# LDO_Regulators.net
KiCad netlist of a schematic drawn in Altium Designer
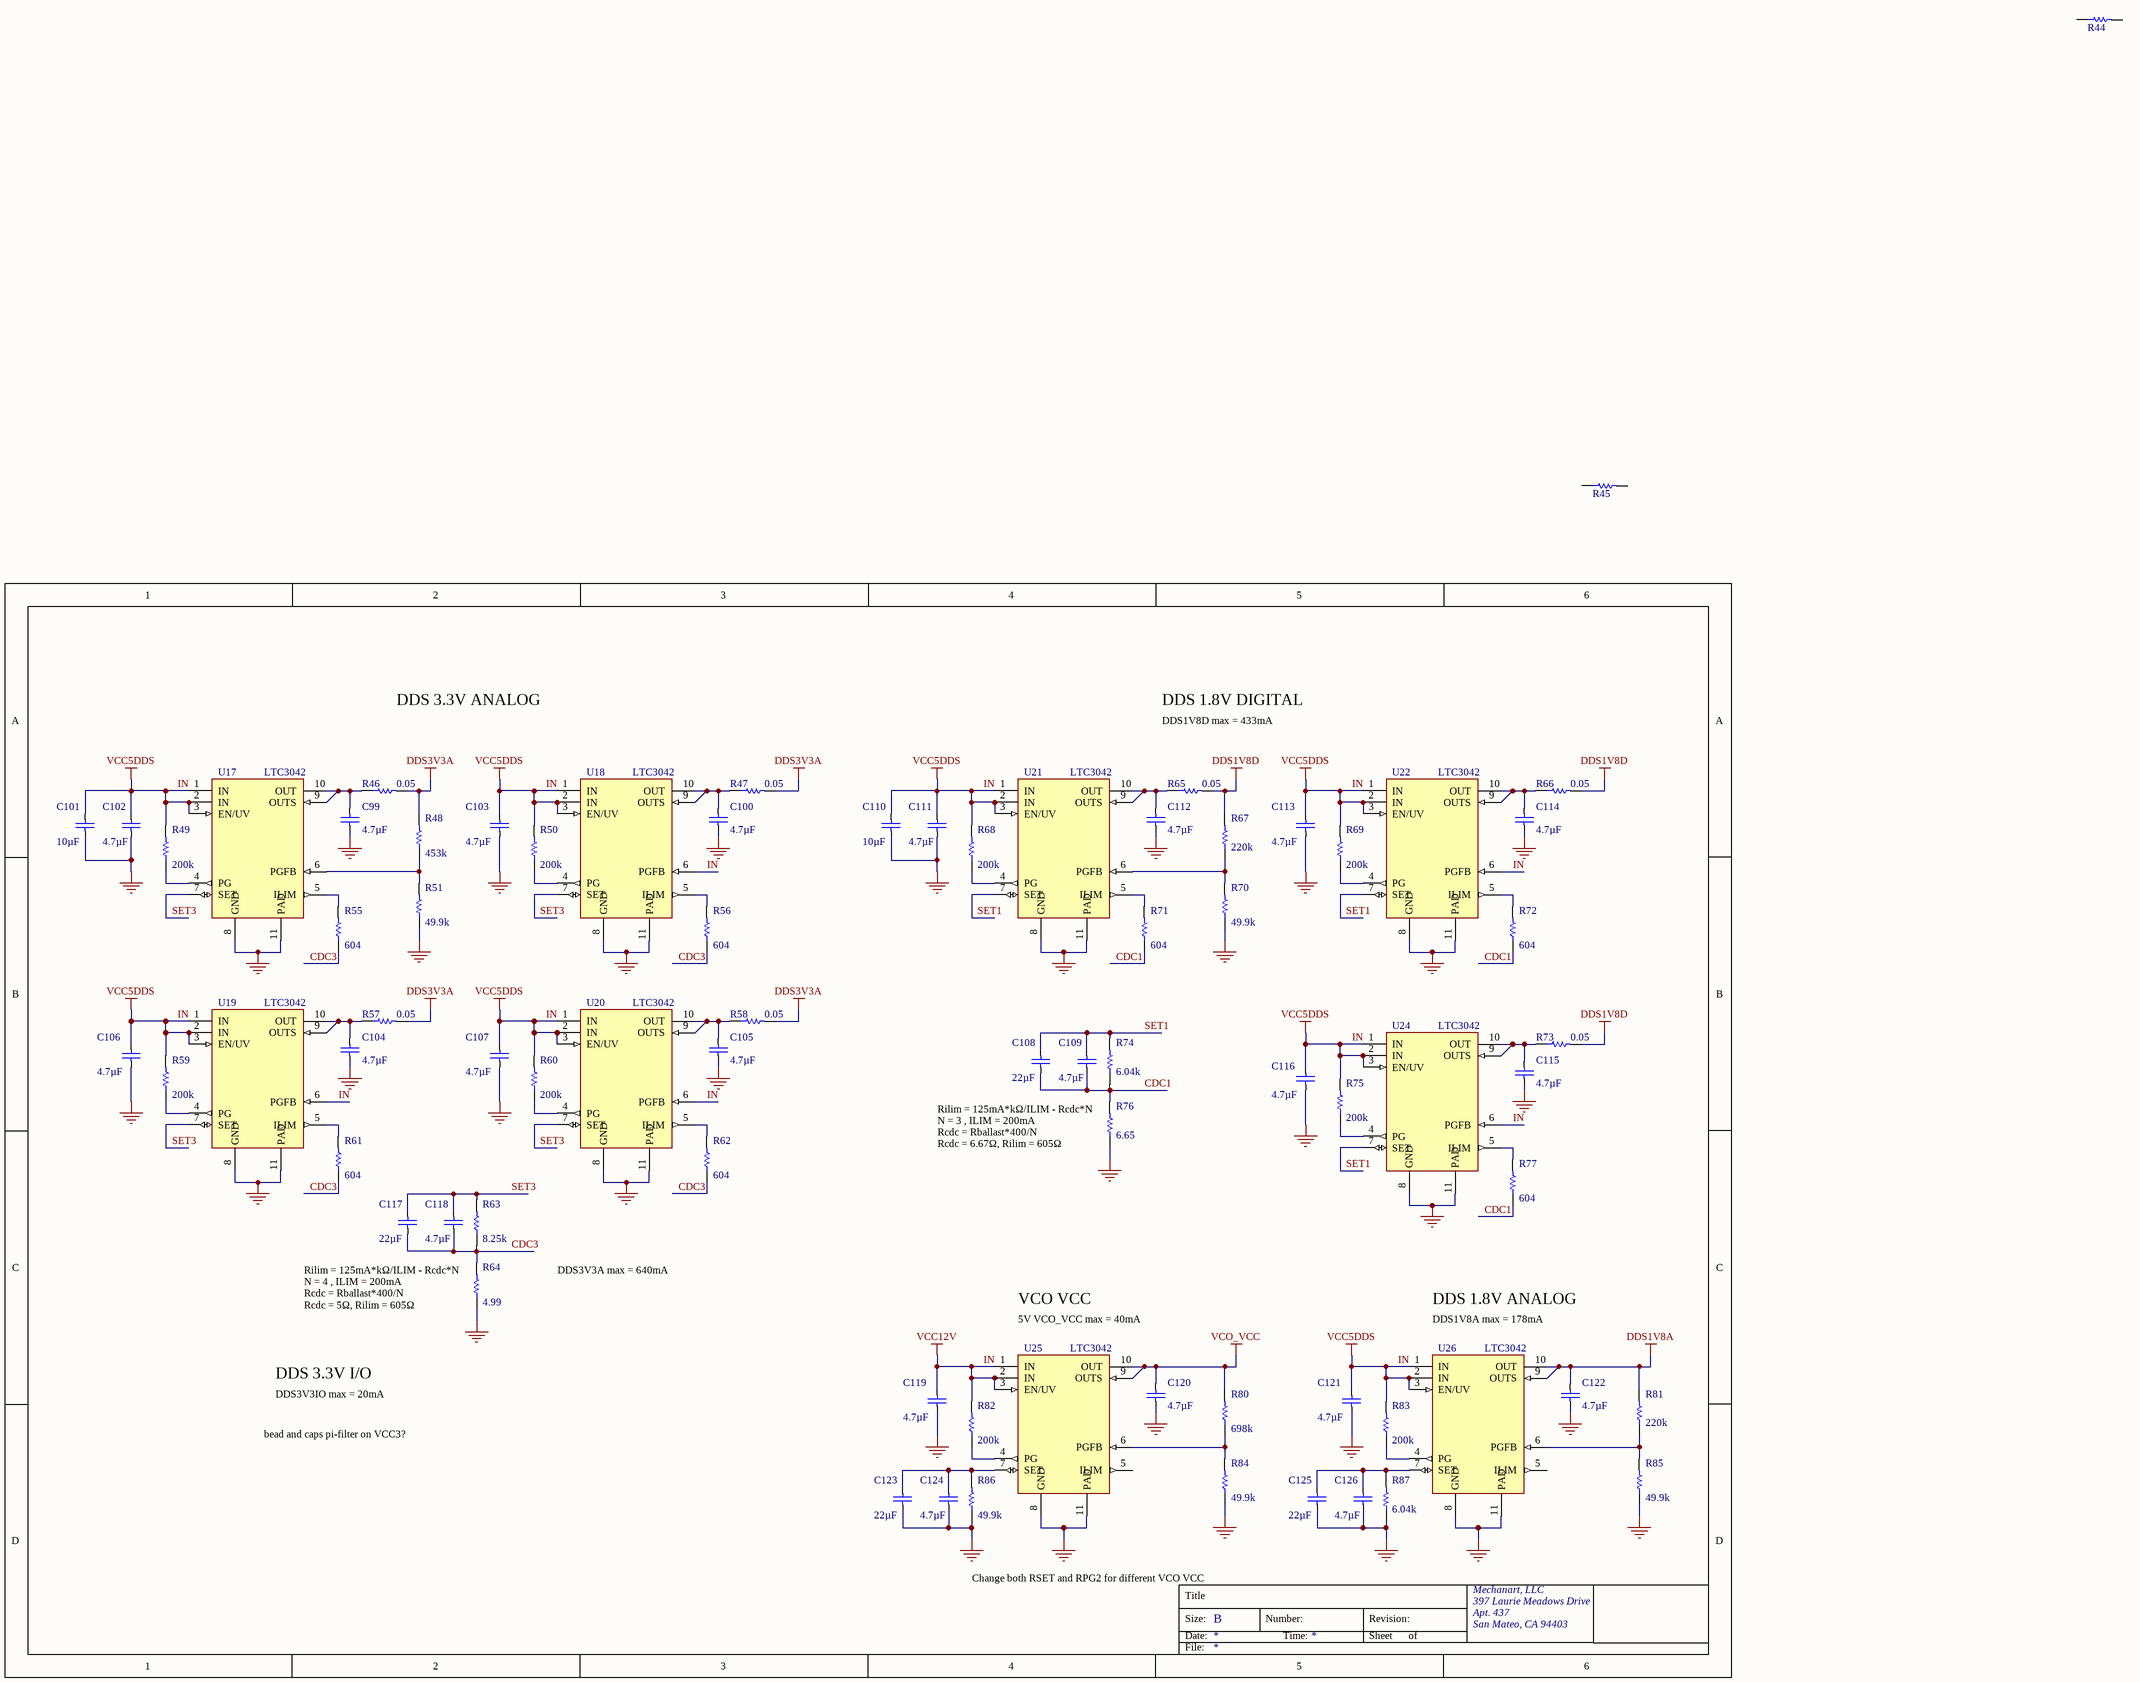
[diagram p0: LDO_Regulators.SchDoc]

(export (version "E")
  (design (tool "Eeschema 10.0.6"))
  (components
    (comp (ref "C99")
      (value "4.7µF")
      (footprint "CAPC3216X160L55N")
      (description "CAP CER 4.7UF 25V X7R 1206")
      (fields
        (field (name "MANUFACTURER") "Murata Electronics North America")
        (field (name "MANUFACTURER PART NUMBER") "GCM31CR71E475KA55L")
      )
      (libsource (lib "mechanart_oshw") (part "CapSMT"))
    )
    (comp (ref "C100")
      (value "4.7µF")
      (footprint "CAPC3216X160L55N")
      (description "CAP CER 4.7UF 25V X7R 1206")
      (fields
        (field (name "MANUFACTURER") "Murata Electronics North America")
        (field (name "MANUFACTURER PART NUMBER") "GCM31CR71E475KA55L")
      )
      (libsource (lib "mechanart_oshw") (part "CapSMT"))
    )
    (comp (ref "C101")
      (value "10µF")
      (footprint "CAPC3216X160L55N")
      (description "CAP CER 10UF 25V X7R 1206")
      (fields
        (field (name "MANUFACTURER") "Murata Electronics North America")
        (field (name "MANUFACTURER PART NUMBER") "GRM31CR71E106KA12L")
      )
      (libsource (lib "mechanart_oshw") (part "CapSMT"))
    )
    (comp (ref "C102")
      (value "4.7µF")
      (footprint "CAPC3216X160L55N")
      (description "CAP CER 4.7UF 25V X7R 1206")
      (fields
        (field (name "MANUFACTURER") "Murata Electronics North America")
        (field (name "MANUFACTURER PART NUMBER") "GCM31CR71E475KA55L")
      )
      (libsource (lib "mechanart_oshw") (part "CapSMT"))
    )
    (comp (ref "C103")
      (value "4.7µF")
      (footprint "CAPC3216X160L55N")
      (description "CAP CER 4.7UF 25V X7R 1206")
      (fields
        (field (name "MANUFACTURER") "Murata Electronics North America")
        (field (name "MANUFACTURER PART NUMBER") "GCM31CR71E475KA55L")
      )
      (libsource (lib "mechanart_oshw") (part "CapSMT"))
    )
    (comp (ref "C104")
      (value "4.7µF")
      (footprint "CAPC3216X160L55N")
      (description "CAP CER 4.7UF 25V X7R 1206")
      (fields
        (field (name "MANUFACTURER") "Murata Electronics North America")
        (field (name "MANUFACTURER PART NUMBER") "GCM31CR71E475KA55L")
      )
      (libsource (lib "mechanart_oshw") (part "CapSMT"))
    )
    (comp (ref "C105")
      (value "4.7µF")
      (footprint "CAPC3216X160L55N")
      (description "CAP CER 4.7UF 25V X7R 1206")
      (fields
        (field (name "MANUFACTURER") "Murata Electronics North America")
        (field (name "MANUFACTURER PART NUMBER") "GCM31CR71E475KA55L")
      )
      (libsource (lib "mechanart_oshw") (part "CapSMT"))
    )
    (comp (ref "C106")
      (value "4.7µF")
      (footprint "CAPC3216X160L55N")
      (description "CAP CER 4.7UF 25V X7R 1206")
      (fields
        (field (name "MANUFACTURER") "Murata Electronics North America")
        (field (name "MANUFACTURER PART NUMBER") "GCM31CR71E475KA55L")
      )
      (libsource (lib "mechanart_oshw") (part "CapSMT"))
    )
    (comp (ref "C107")
      (value "4.7µF")
      (footprint "CAPC3216X160L55N")
      (description "CAP CER 4.7UF 25V X7R 1206")
      (fields
        (field (name "MANUFACTURER") "Murata Electronics North America")
        (field (name "MANUFACTURER PART NUMBER") "GCM31CR71E475KA55L")
      )
      (libsource (lib "mechanart_oshw") (part "CapSMT"))
    )
    (comp (ref "C108")
      (value "22µF")
      (footprint "CAPC2012X145L30N")
      (description "CAP CER 22UF 16V X5R 0805")
      (fields
        (field (name "MANUFACTURER") "TDK Corporation")
        (field (name "MANUFACTURER PART NUMBER") "C2012X5R1C226K125AC")
      )
      (libsource (lib "mechanart_oshw") (part "CapSMT"))
    )
    (comp (ref "C109")
      (value "4.7µF")
      (footprint "CAPC3216X160L55N")
      (description "CAP CER 4.7UF 25V X7R 1206")
      (fields
        (field (name "MANUFACTURER") "Murata Electronics North America")
        (field (name "MANUFACTURER PART NUMBER") "GCM31CR71E475KA55L")
      )
      (libsource (lib "mechanart_oshw") (part "CapSMT"))
    )
    (comp (ref "C110")
      (value "10µF")
      (footprint "CAPC3216X160L55N")
      (description "CAP CER 10UF 25V X7R 1206")
      (fields
        (field (name "MANUFACTURER") "Murata Electronics North America")
        (field (name "MANUFACTURER PART NUMBER") "GRM31CR71E106KA12L")
      )
      (libsource (lib "mechanart_oshw") (part "CapSMT"))
    )
    (comp (ref "C111")
      (value "4.7µF")
      (footprint "CAPC3216X160L55N")
      (description "CAP CER 4.7UF 25V X7R 1206")
      (fields
        (field (name "MANUFACTURER") "Murata Electronics North America")
        (field (name "MANUFACTURER PART NUMBER") "GCM31CR71E475KA55L")
      )
      (libsource (lib "mechanart_oshw") (part "CapSMT"))
    )
    (comp (ref "C112")
      (value "4.7µF")
      (footprint "CAPC3216X160L55N")
      (description "CAP CER 4.7UF 25V X7R 1206")
      (fields
        (field (name "MANUFACTURER") "Murata Electronics North America")
        (field (name "MANUFACTURER PART NUMBER") "GCM31CR71E475KA55L")
      )
      (libsource (lib "mechanart_oshw") (part "CapSMT"))
    )
    (comp (ref "C113")
      (value "4.7µF")
      (footprint "CAPC3216X160L55N")
      (description "CAP CER 4.7UF 25V X7R 1206")
      (fields
        (field (name "MANUFACTURER") "Murata Electronics North America")
        (field (name "MANUFACTURER PART NUMBER") "GCM31CR71E475KA55L")
      )
      (libsource (lib "mechanart_oshw") (part "CapSMT"))
    )
    (comp (ref "C114")
      (value "4.7µF")
      (footprint "CAPC3216X160L55N")
      (description "CAP CER 4.7UF 25V X7R 1206")
      (fields
        (field (name "MANUFACTURER") "Murata Electronics North America")
        (field (name "MANUFACTURER PART NUMBER") "GCM31CR71E475KA55L")
      )
      (libsource (lib "mechanart_oshw") (part "CapSMT"))
    )
    (comp (ref "C115")
      (value "4.7µF")
      (footprint "CAPC3216X160L55N")
      (description "CAP CER 4.7UF 25V X7R 1206")
      (fields
        (field (name "MANUFACTURER") "Murata Electronics North America")
        (field (name "MANUFACTURER PART NUMBER") "GCM31CR71E475KA55L")
      )
      (libsource (lib "mechanart_oshw") (part "CapSMT"))
    )
    (comp (ref "C116")
      (value "4.7µF")
      (footprint "CAPC3216X160L55N")
      (description "CAP CER 4.7UF 25V X7R 1206")
      (fields
        (field (name "MANUFACTURER") "Murata Electronics North America")
        (field (name "MANUFACTURER PART NUMBER") "GCM31CR71E475KA55L")
      )
      (libsource (lib "mechanart_oshw") (part "CapSMT"))
    )
    (comp (ref "C117")
      (value "22µF")
      (footprint "CAPC2012X145L30N")
      (description "CAP CER 22UF 16V X5R 0805")
      (fields
        (field (name "MANUFACTURER") "TDK Corporation")
        (field (name "MANUFACTURER PART NUMBER") "C2012X5R1C226K125AC")
      )
      (libsource (lib "mechanart_oshw") (part "CapSMT"))
    )
    (comp (ref "C118")
      (value "4.7µF")
      (footprint "CAPC3216X160L55N")
      (description "CAP CER 4.7UF 25V X7R 1206")
      (fields
        (field (name "MANUFACTURER") "Murata Electronics North America")
        (field (name "MANUFACTURER PART NUMBER") "GCM31CR71E475KA55L")
      )
      (libsource (lib "mechanart_oshw") (part "CapSMT"))
    )
    (comp (ref "C119")
      (value "4.7µF")
      (footprint "CAPC3216X160L55N")
      (description "CAP CER 4.7UF 25V X7R 1206")
      (fields
        (field (name "MANUFACTURER") "Murata Electronics North America")
        (field (name "MANUFACTURER PART NUMBER") "GCM31CR71E475KA55L")
      )
      (libsource (lib "mechanart_oshw") (part "CapSMT"))
    )
    (comp (ref "C120")
      (value "4.7µF")
      (footprint "CAPC3216X160L55N")
      (description "CAP CER 4.7UF 25V X7R 1206")
      (fields
        (field (name "MANUFACTURER") "Murata Electronics North America")
        (field (name "MANUFACTURER PART NUMBER") "GCM31CR71E475KA55L")
      )
      (libsource (lib "mechanart_oshw") (part "CapSMT"))
    )
    (comp (ref "C121")
      (value "4.7µF")
      (footprint "CAPC3216X160L55N")
      (description "CAP CER 4.7UF 25V X7R 1206")
      (fields
        (field (name "MANUFACTURER") "Murata Electronics North America")
        (field (name "MANUFACTURER PART NUMBER") "GCM31CR71E475KA55L")
      )
      (libsource (lib "mechanart_oshw") (part "CapSMT"))
    )
    (comp (ref "C122")
      (value "4.7µF")
      (footprint "CAPC3216X160L55N")
      (description "CAP CER 4.7UF 25V X7R 1206")
      (fields
        (field (name "MANUFACTURER") "Murata Electronics North America")
        (field (name "MANUFACTURER PART NUMBER") "GCM31CR71E475KA55L")
      )
      (libsource (lib "mechanart_oshw") (part "CapSMT"))
    )
    (comp (ref "C123")
      (value "22µF")
      (footprint "CAPC2012X145L30N")
      (description "CAP CER 22UF 16V X5R 0805")
      (fields
        (field (name "MANUFACTURER") "TDK Corporation")
        (field (name "MANUFACTURER PART NUMBER") "C2012X5R1C226K125AC")
      )
      (libsource (lib "mechanart_oshw") (part "CapSMT"))
    )
    (comp (ref "C124")
      (value "4.7µF")
      (footprint "CAPC3216X160L55N")
      (description "CAP CER 4.7UF 25V X7R 1206")
      (fields
        (field (name "MANUFACTURER") "Murata Electronics North America")
        (field (name "MANUFACTURER PART NUMBER") "GCM31CR71E475KA55L")
      )
      (libsource (lib "mechanart_oshw") (part "CapSMT"))
    )
    (comp (ref "C125")
      (value "22µF")
      (footprint "CAPC2012X145L30N")
      (description "CAP CER 22UF 16V X5R 0805")
      (fields
        (field (name "MANUFACTURER") "TDK Corporation")
        (field (name "MANUFACTURER PART NUMBER") "C2012X5R1C226K125AC")
      )
      (libsource (lib "mechanart_oshw") (part "CapSMT"))
    )
    (comp (ref "C126")
      (value "4.7µF")
      (footprint "CAPC3216X160L55N")
      (description "CAP CER 4.7UF 25V X7R 1206")
      (fields
        (field (name "MANUFACTURER") "Murata Electronics North America")
        (field (name "MANUFACTURER PART NUMBER") "GCM31CR71E475KA55L")
      )
      (libsource (lib "mechanart_oshw") (part "CapSMT"))
    )
    (comp (ref "R44")
      (value "0.05")
      (footprint "RESC_2012[0805]_N")
      (description "RES SMD 0.05 OHM 1% 1/4W 0805")
      (fields
        (field (name "MANUFACTURER") "Vishay Dale")
        (field (name "MANUFACTURER PART NUMBER") "WSL0805R0500FEA18")
      )
      (libsource (lib "mechanart_oshw") (part "ResSMT"))
    )
    (comp (ref "R45")
      (value "8.25k")
      (footprint "RESC1608X45L30N")
      (description "RES SMD 8.25K OHM 1% 1/10W 0603")
      (fields
        (field (name "MANUFACTURER") "Vishay Dale")
        (field (name "MANUFACTURER PART NUMBER") "CRCW06038K25FKEA")
      )
      (libsource (lib "mechanart_oshw") (part "ResSMT"))
    )
    (comp (ref "R46")
      (value "0.05")
      (footprint "RESC_2012[0805]_N")
      (description "RES SMD 0.05 OHM 1% 1/4W 0805")
      (fields
        (field (name "MANUFACTURER") "Vishay Dale")
        (field (name "MANUFACTURER PART NUMBER") "WSL0805R0500FEA18")
      )
      (libsource (lib "mechanart_oshw") (part "ResSMT"))
    )
    (comp (ref "R47")
      (value "0.05")
      (footprint "RESC_2012[0805]_N")
      (description "RES SMD 0.05 OHM 1% 1/4W 0805")
      (fields
        (field (name "MANUFACTURER") "Vishay Dale")
        (field (name "MANUFACTURER PART NUMBER") "WSL0805R0500FEA18")
      )
      (libsource (lib "mechanart_oshw") (part "ResSMT"))
    )
    (comp (ref "R48")
      (value "453k")
      (footprint "RESC1608X45L30N")
      (description "RES SMD 453K OHM 1% 1/10W 0603")
      (fields
        (field (name "MANUFACTURER") "Vishay Dale")
        (field (name "MANUFACTURER PART NUMBER") "CRCW0603453KFKEA")
      )
      (libsource (lib "mechanart_oshw") (part "ResSMT"))
    )
    (comp (ref "R49")
      (value "200k")
      (footprint "RESC1608X45L30N")
      (description "RES SMD 200K OHM 1% 1/10W 0603")
      (fields
        (field (name "MANUFACTURER") "Vishay Dale")
        (field (name "MANUFACTURER PART NUMBER") "CRCW0603200KFKEA")
      )
      (libsource (lib "mechanart_oshw") (part "ResSMT"))
    )
    (comp (ref "R50")
      (value "200k")
      (footprint "RESC1608X45L30N")
      (description "RES SMD 200K OHM 1% 1/10W 0603")
      (fields
        (field (name "MANUFACTURER") "Vishay Dale")
        (field (name "MANUFACTURER PART NUMBER") "CRCW0603200KFKEA")
      )
      (libsource (lib "mechanart_oshw") (part "ResSMT"))
    )
    (comp (ref "R51")
      (value "49.9k")
      (footprint "RESC1608X45L30N")
      (description "RES SMD 49.9K OHM 1% 1/10W 0603")
      (fields
        (field (name "MANUFACTURER") "Vishay Dale")
        (field (name "MANUFACTURER PART NUMBER") "CRCW060349K9FKEA")
      )
      (libsource (lib "mechanart_oshw") (part "ResSMT"))
    )
    (comp (ref "R55")
      (value "604")
      (footprint "RESC1608X45L30N")
      (description "RES SMD 604 OHM 1% 1/10W 0603")
      (fields
        (field (name "MANUFACTURER") "Vishay Dale")
        (field (name "MANUFACTURER PART NUMBER") "CRCW0603604RFKEA")
      )
      (libsource (lib "mechanart_oshw") (part "ResSMT"))
    )
    (comp (ref "R56")
      (value "604")
      (footprint "RESC1608X45L30N")
      (description "RES SMD 604 OHM 1% 1/10W 0603")
      (fields
        (field (name "MANUFACTURER") "Vishay Dale")
        (field (name "MANUFACTURER PART NUMBER") "CRCW0603604RFKEA")
      )
      (libsource (lib "mechanart_oshw") (part "ResSMT"))
    )
    (comp (ref "R57")
      (value "0.05")
      (footprint "RESC_2012[0805]_N")
      (description "RES SMD 0.05 OHM 1% 1/4W 0805")
      (fields
        (field (name "MANUFACTURER") "Vishay Dale")
        (field (name "MANUFACTURER PART NUMBER") "WSL0805R0500FEA18")
      )
      (libsource (lib "mechanart_oshw") (part "ResSMT"))
    )
    (comp (ref "R58")
      (value "0.05")
      (footprint "RESC_2012[0805]_N")
      (description "RES SMD 0.05 OHM 1% 1/4W 0805")
      (fields
        (field (name "MANUFACTURER") "Vishay Dale")
        (field (name "MANUFACTURER PART NUMBER") "WSL0805R0500FEA18")
      )
      (libsource (lib "mechanart_oshw") (part "ResSMT"))
    )
    (comp (ref "R59")
      (value "200k")
      (footprint "RESC1608X45L30N")
      (description "RES SMD 200K OHM 1% 1/10W 0603")
      (fields
        (field (name "MANUFACTURER") "Vishay Dale")
        (field (name "MANUFACTURER PART NUMBER") "CRCW0603200KFKEA")
      )
      (libsource (lib "mechanart_oshw") (part "ResSMT"))
    )
    (comp (ref "R60")
      (value "200k")
      (footprint "RESC1608X45L30N")
      (description "RES SMD 200K OHM 1% 1/10W 0603")
      (fields
        (field (name "MANUFACTURER") "Vishay Dale")
        (field (name "MANUFACTURER PART NUMBER") "CRCW0603200KFKEA")
      )
      (libsource (lib "mechanart_oshw") (part "ResSMT"))
    )
    (comp (ref "R61")
      (value "604")
      (footprint "RESC1608X45L30N")
      (description "RES SMD 604 OHM 1% 1/10W 0603")
      (fields
        (field (name "MANUFACTURER") "Vishay Dale")
        (field (name "MANUFACTURER PART NUMBER") "CRCW0603604RFKEA")
      )
      (libsource (lib "mechanart_oshw") (part "ResSMT"))
    )
    (comp (ref "R62")
      (value "604")
      (footprint "RESC1608X45L30N")
      (description "RES SMD 604 OHM 1% 1/10W 0603")
      (fields
        (field (name "MANUFACTURER") "Vishay Dale")
        (field (name "MANUFACTURER PART NUMBER") "CRCW0603604RFKEA")
      )
      (libsource (lib "mechanart_oshw") (part "ResSMT"))
    )
    (comp (ref "R63")
      (value "8.25k")
      (footprint "RESC1608X45L30N")
      (description "RES SMD 8.25K OHM 1% 1/10W 0603")
      (fields
        (field (name "MANUFACTURER") "Vishay Dale")
        (field (name "MANUFACTURER PART NUMBER") "CRCW06038K25FKEA")
      )
      (libsource (lib "mechanart_oshw") (part "ResSMT"))
    )
    (comp (ref "R64")
      (value "4.99")
      (footprint "RESC1608X45L30N")
      (description "RES SMD 4.99 OHM 1% 1/10W 0603")
      (fields
        (field (name "MANUFACTURER") "Vishay Dale")
        (field (name "MANUFACTURER PART NUMBER") "CRCW06034R99FKEA")
      )
      (libsource (lib "mechanart_oshw") (part "ResSMT"))
    )
    (comp (ref "R65")
      (value "0.05")
      (footprint "RESC_2012[0805]_N")
      (description "RES SMD 0.05 OHM 1% 1/4W 0805")
      (fields
        (field (name "MANUFACTURER") "Vishay Dale")
        (field (name "MANUFACTURER PART NUMBER") "WSL0805R0500FEA18")
      )
      (libsource (lib "mechanart_oshw") (part "ResSMT"))
    )
    (comp (ref "R66")
      (value "0.05")
      (footprint "RESC_2012[0805]_N")
      (description "RES SMD 0.05 OHM 1% 1/4W 0805")
      (fields
        (field (name "MANUFACTURER") "Vishay Dale")
        (field (name "MANUFACTURER PART NUMBER") "WSL0805R0500FEA18")
      )
      (libsource (lib "mechanart_oshw") (part "ResSMT"))
    )
    (comp (ref "R67")
      (value "220k")
      (footprint "RESC1608X45L30N")
      (description "RES SMD 220K OHM 1% 1/10W 0603")
      (fields
        (field (name "MANUFACTURER") "Vishay Dale")
        (field (name "MANUFACTURER PART NUMBER") "CRCW0603220KFKEA")
      )
      (libsource (lib "mechanart_oshw") (part "ResSMT"))
    )
    (comp (ref "R68")
      (value "200k")
      (footprint "RESC1608X45L30N")
      (description "RES SMD 200K OHM 1% 1/10W 0603")
      (fields
        (field (name "MANUFACTURER") "Vishay Dale")
        (field (name "MANUFACTURER PART NUMBER") "CRCW0603200KFKEA")
      )
      (libsource (lib "mechanart_oshw") (part "ResSMT"))
    )
    (comp (ref "R69")
      (value "200k")
      (footprint "RESC1608X45L30N")
      (description "RES SMD 200K OHM 1% 1/10W 0603")
      (fields
        (field (name "MANUFACTURER") "Vishay Dale")
        (field (name "MANUFACTURER PART NUMBER") "CRCW0603200KFKEA")
      )
      (libsource (lib "mechanart_oshw") (part "ResSMT"))
    )
    (comp (ref "R70")
      (value "49.9k")
      (footprint "RESC1608X45L30N")
      (description "RES SMD 49.9K OHM 1% 1/10W 0603")
      (fields
        (field (name "MANUFACTURER") "Vishay Dale")
        (field (name "MANUFACTURER PART NUMBER") "CRCW060349K9FKEA")
      )
      (libsource (lib "mechanart_oshw") (part "ResSMT"))
    )
    (comp (ref "R71")
      (value "604")
      (footprint "RESC1608X45L30N")
      (description "RES SMD 604 OHM 1% 1/10W 0603")
      (fields
        (field (name "MANUFACTURER") "Vishay Dale")
        (field (name "MANUFACTURER PART NUMBER") "CRCW0603604RFKEA")
      )
      (libsource (lib "mechanart_oshw") (part "ResSMT"))
    )
    (comp (ref "R72")
      (value "604")
      (footprint "RESC1608X45L30N")
      (description "RES SMD 604 OHM 1% 1/10W 0603")
      (fields
        (field (name "MANUFACTURER") "Vishay Dale")
        (field (name "MANUFACTURER PART NUMBER") "CRCW0603604RFKEA")
      )
      (libsource (lib "mechanart_oshw") (part "ResSMT"))
    )
    (comp (ref "R73")
      (value "0.05")
      (footprint "RESC_2012[0805]_N")
      (description "RES SMD 0.05 OHM 1% 1/4W 0805")
      (fields
        (field (name "MANUFACTURER") "Vishay Dale")
        (field (name "MANUFACTURER PART NUMBER") "WSL0805R0500FEA18")
      )
      (libsource (lib "mechanart_oshw") (part "ResSMT"))
    )
    (comp (ref "R74")
      (value "6.04k")
      (footprint "RESC1608X45L30N")
      (description "RES SMD 6.04K OHM 1% 1/10W 0603")
      (fields
        (field (name "MANUFACTURER") "Vishay Dale")
        (field (name "MANUFACTURER PART NUMBER") "CRCW06036K04FKEA")
      )
      (libsource (lib "mechanart_oshw") (part "ResSMT"))
    )
    (comp (ref "R75")
      (value "200k")
      (footprint "RESC1608X45L30N")
      (description "RES SMD 200K OHM 1% 1/10W 0603")
      (fields
        (field (name "MANUFACTURER") "Vishay Dale")
        (field (name "MANUFACTURER PART NUMBER") "CRCW0603200KFKEA")
      )
      (libsource (lib "mechanart_oshw") (part "ResSMT"))
    )
    (comp (ref "R76")
      (value "6.65")
      (footprint "RESC1608X45L30N")
      (description "RES SMD 6.65 OHM 1% 1/10W 0603")
      (fields
        (field (name "MANUFACTURER") "Vishay Dale")
        (field (name "MANUFACTURER PART NUMBER") "CRCW06036R65FKEA")
      )
      (libsource (lib "mechanart_oshw") (part "ResSMT"))
    )
    (comp (ref "R77")
      (value "604")
      (footprint "RESC1608X45L30N")
      (description "RES SMD 604 OHM 1% 1/10W 0603")
      (fields
        (field (name "MANUFACTURER") "Vishay Dale")
        (field (name "MANUFACTURER PART NUMBER") "CRCW0603604RFKEA")
      )
      (libsource (lib "mechanart_oshw") (part "ResSMT"))
    )
    (comp (ref "R80")
      (value "698k")
      (footprint "RESC1608X45L30N")
      (description "RES SMD 698K OHM 1% 1/10W 0603")
      (fields
        (field (name "MANUFACTURER") "Vishay Dale")
        (field (name "MANUFACTURER PART NUMBER") "CRCW0603698KFKEA")
      )
      (libsource (lib "mechanart_oshw") (part "ResSMT"))
    )
    (comp (ref "R81")
      (value "220k")
      (footprint "RESC1608X45L30N")
      (description "RES SMD 220K OHM 1% 1/10W 0603")
      (fields
        (field (name "MANUFACTURER") "Vishay Dale")
        (field (name "MANUFACTURER PART NUMBER") "CRCW0603220KFKEA")
      )
      (libsource (lib "mechanart_oshw") (part "ResSMT"))
    )
    (comp (ref "R82")
      (value "200k")
      (footprint "RESC1608X45L30N")
      (description "RES SMD 200K OHM 1% 1/10W 0603")
      (fields
        (field (name "MANUFACTURER") "Vishay Dale")
        (field (name "MANUFACTURER PART NUMBER") "CRCW0603200KFKEA")
      )
      (libsource (lib "mechanart_oshw") (part "ResSMT"))
    )
    (comp (ref "R83")
      (value "200k")
      (footprint "RESC1608X45L30N")
      (description "RES SMD 200K OHM 1% 1/10W 0603")
      (fields
        (field (name "MANUFACTURER") "Vishay Dale")
        (field (name "MANUFACTURER PART NUMBER") "CRCW0603200KFKEA")
      )
      (libsource (lib "mechanart_oshw") (part "ResSMT"))
    )
    (comp (ref "R84")
      (value "49.9k")
      (footprint "RESC1608X45L30N")
      (description "RES SMD 49.9K OHM 1% 1/10W 0603")
      (fields
        (field (name "MANUFACTURER") "Vishay Dale")
        (field (name "MANUFACTURER PART NUMBER") "CRCW060349K9FKEA")
      )
      (libsource (lib "mechanart_oshw") (part "ResSMT"))
    )
    (comp (ref "R85")
      (value "49.9k")
      (footprint "RESC1608X45L30N")
      (description "RES SMD 49.9K OHM 1% 1/10W 0603")
      (fields
        (field (name "MANUFACTURER") "Vishay Dale")
        (field (name "MANUFACTURER PART NUMBER") "CRCW060349K9FKEA")
      )
      (libsource (lib "mechanart_oshw") (part "ResSMT"))
    )
    (comp (ref "R86")
      (value "49.9k")
      (footprint "RESC1608X45L30N")
      (description "RES SMD 49.9K OHM 1% 1/10W 0603")
      (fields
        (field (name "MANUFACTURER") "Vishay Dale")
        (field (name "MANUFACTURER PART NUMBER") "CRCW060349K9FKEA")
      )
      (libsource (lib "mechanart_oshw") (part "ResSMT"))
    )
    (comp (ref "R87")
      (value "6.04k")
      (footprint "RESC1608X45L30N")
      (description "RES SMD 6.04K OHM 1% 1/10W 0603")
      (fields
        (field (name "MANUFACTURER") "Vishay Dale")
        (field (name "MANUFACTURER PART NUMBER") "CRCW06036K04FKEA")
      )
      (libsource (lib "mechanart_oshw") (part "ResSMT"))
    )
    (comp (ref "U17")
      (value "LTC3042")
      (footprint "SON50P300X300X75-11T175X248L")
      (description "IC REG LDO ADJ 0.2A 10DFN")
      (fields
        (field (name "MANUFACTURER") "Linear Technology")
        (field (name "MANUFACTURER PART NUMBER") "LT3042EDD#PBF")
      )
      (libsource (lib "mechanart_oshw") (part "LTC3042"))
    )
    (comp (ref "U18")
      (value "LTC3042")
      (footprint "SON50P300X300X75-11T175X248L")
      (description "IC REG LDO ADJ 0.2A 10DFN")
      (fields
        (field (name "MANUFACTURER") "Linear Technology")
        (field (name "MANUFACTURER PART NUMBER") "LT3042EDD#PBF")
      )
      (libsource (lib "mechanart_oshw") (part "LTC3042"))
    )
    (comp (ref "U19")
      (value "LTC3042")
      (footprint "SON50P300X300X75-11T175X248L")
      (description "IC REG LDO ADJ 0.2A 10DFN")
      (fields
        (field (name "MANUFACTURER") "Linear Technology")
        (field (name "MANUFACTURER PART NUMBER") "LT3042EDD#PBF")
      )
      (libsource (lib "mechanart_oshw") (part "LTC3042"))
    )
    (comp (ref "U20")
      (value "LTC3042")
      (footprint "SON50P300X300X75-11T175X248L")
      (description "IC REG LDO ADJ 0.2A 10DFN")
      (fields
        (field (name "MANUFACTURER") "Linear Technology")
        (field (name "MANUFACTURER PART NUMBER") "LT3042EDD#PBF")
      )
      (libsource (lib "mechanart_oshw") (part "LTC3042"))
    )
    (comp (ref "U21")
      (value "LTC3042")
      (footprint "SON50P300X300X75-11T175X248L")
      (description "IC REG LDO ADJ 0.2A 10DFN")
      (fields
        (field (name "MANUFACTURER") "Linear Technology")
        (field (name "MANUFACTURER PART NUMBER") "LT3042EDD#PBF")
      )
      (libsource (lib "mechanart_oshw") (part "LTC3042"))
    )
    (comp (ref "U22")
      (value "LTC3042")
      (footprint "SON50P300X300X75-11T175X248L")
      (description "IC REG LDO ADJ 0.2A 10DFN")
      (fields
        (field (name "MANUFACTURER") "Linear Technology")
        (field (name "MANUFACTURER PART NUMBER") "LT3042EDD#PBF")
      )
      (libsource (lib "mechanart_oshw") (part "LTC3042"))
    )
    (comp (ref "U24")
      (value "LTC3042")
      (footprint "SON50P300X300X75-11T175X248L")
      (description "IC REG LDO ADJ 0.2A 10DFN")
      (fields
        (field (name "MANUFACTURER") "Linear Technology")
        (field (name "MANUFACTURER PART NUMBER") "LT3042EDD#PBF")
      )
      (libsource (lib "mechanart_oshw") (part "LTC3042"))
    )
    (comp (ref "U25")
      (value "LTC3042")
      (footprint "SON50P300X300X75-11T175X248L")
      (description "IC REG LDO ADJ 0.2A 10DFN")
      (fields
        (field (name "MANUFACTURER") "Linear Technology")
        (field (name "MANUFACTURER PART NUMBER") "LT3042EDD#PBF")
      )
      (libsource (lib "mechanart_oshw") (part "LTC3042"))
    )
    (comp (ref "U26")
      (value "LTC3042")
      (footprint "SON50P300X300X75-11T175X248L")
      (description "IC REG LDO ADJ 0.2A 10DFN")
      (fields
        (field (name "MANUFACTURER") "Linear Technology")
        (field (name "MANUFACTURER PART NUMBER") "LT3042EDD#PBF")
      )
      (libsource (lib "mechanart_oshw") (part "LTC3042"))
    )
  )
  (nets
    (net (code "1") (name "/CDC1") (class "Default")
      (node (ref "C108") (pin "2") (pinfunction "2_2") (pintype "passive"))
      (node (ref "C109") (pin "2") (pinfunction "2_2") (pintype "passive"))
      (node (ref "R71") (pin "1") (pinfunction "1_1") (pintype "passive"))
      (node (ref "R72") (pin "1") (pinfunction "1_1") (pintype "passive"))
      (node (ref "R74") (pin "1") (pinfunction "1_1") (pintype "passive"))
      (node (ref "R76") (pin "2") (pinfunction "2_2") (pintype "passive"))
      (node (ref "R77") (pin "1") (pinfunction "1_1") (pintype "passive"))
    )
    (net (code "2") (name "/CDC3") (class "Default")
      (node (ref "C117") (pin "2") (pinfunction "2_2") (pintype "passive"))
      (node (ref "C118") (pin "2") (pinfunction "2_2") (pintype "passive"))
      (node (ref "R55") (pin "1") (pinfunction "1_1") (pintype "passive"))
      (node (ref "R56") (pin "1") (pinfunction "1_1") (pintype "passive"))
      (node (ref "R61") (pin "1") (pinfunction "1_1") (pintype "passive"))
      (node (ref "R62") (pin "1") (pinfunction "1_1") (pintype "passive"))
      (node (ref "R63") (pin "1") (pinfunction "1_1") (pintype "passive"))
      (node (ref "R64") (pin "2") (pinfunction "2_2") (pintype "passive"))
    )
    (net (code "3") (name "/SET1") (class "Default")
      (node (ref "C108") (pin "1") (pinfunction "1_1") (pintype "passive"))
      (node (ref "C109") (pin "1") (pinfunction "1_1") (pintype "passive"))
      (node (ref "R74") (pin "2") (pinfunction "2_2") (pintype "passive"))
      (node (ref "U21") (pin "7") (pinfunction "SET_7") (pintype "bidirectional"))
      (node (ref "U22") (pin "7") (pinfunction "SET_7") (pintype "bidirectional"))
      (node (ref "U24") (pin "7") (pinfunction "SET_7") (pintype "bidirectional"))
    )
    (net (code "4") (name "/SET3") (class "Default")
      (node (ref "C117") (pin "1") (pinfunction "1_1") (pintype "passive"))
      (node (ref "C118") (pin "1") (pinfunction "1_1") (pintype "passive"))
      (node (ref "R63") (pin "2") (pinfunction "2_2") (pintype "passive"))
      (node (ref "U17") (pin "7") (pinfunction "SET_7") (pintype "bidirectional"))
      (node (ref "U18") (pin "7") (pinfunction "SET_7") (pintype "bidirectional"))
      (node (ref "U19") (pin "7") (pinfunction "SET_7") (pintype "bidirectional"))
      (node (ref "U20") (pin "7") (pinfunction "SET_7") (pintype "bidirectional"))
    )
    (net (code "5") (name "DDS1V8A") (class "Default")
      (node (ref "C122") (pin "1") (pinfunction "1_1") (pintype "passive"))
      (node (ref "R81") (pin "2") (pinfunction "2_2") (pintype "passive"))
      (node (ref "U26") (pin "10") (pinfunction "OUT_10") (pintype "power_in"))
      (node (ref "U26") (pin "9") (pinfunction "OUTS_9") (pintype "input"))
    )
    (net (code "6") (name "DDS1V8D") (class "Default")
      (node (ref "R65") (pin "2") (pinfunction "2_2") (pintype "passive"))
      (node (ref "R66") (pin "2") (pinfunction "2_2") (pintype "passive"))
      (node (ref "R67") (pin "2") (pinfunction "2_2") (pintype "passive"))
      (node (ref "R73") (pin "2") (pinfunction "2_2") (pintype "passive"))
    )
    (net (code "7") (name "DDS3V3A") (class "Default")
      (node (ref "R46") (pin "2") (pinfunction "2_2") (pintype "passive"))
      (node (ref "R47") (pin "2") (pinfunction "2_2") (pintype "passive"))
      (node (ref "R48") (pin "2") (pinfunction "2_2") (pintype "passive"))
      (node (ref "R57") (pin "2") (pinfunction "2_2") (pintype "passive"))
      (node (ref "R58") (pin "2") (pinfunction "2_2") (pintype "passive"))
    )
    (net (code "8") (name "GND") (class "Default")
      (node (ref "C100") (pin "2") (pinfunction "2_2") (pintype "passive"))
      (node (ref "C101") (pin "2") (pinfunction "2_2") (pintype "passive"))
      (node (ref "C102") (pin "2") (pinfunction "2_2") (pintype "passive"))
      (node (ref "C103") (pin "2") (pinfunction "2_2") (pintype "passive"))
      (node (ref "C104") (pin "2") (pinfunction "2_2") (pintype "passive"))
      (node (ref "C105") (pin "2") (pinfunction "2_2") (pintype "passive"))
      (node (ref "C106") (pin "2") (pinfunction "2_2") (pintype "passive"))
      (node (ref "C107") (pin "2") (pinfunction "2_2") (pintype "passive"))
      (node (ref "C110") (pin "2") (pinfunction "2_2") (pintype "passive"))
      (node (ref "C111") (pin "2") (pinfunction "2_2") (pintype "passive"))
      (node (ref "C112") (pin "2") (pinfunction "2_2") (pintype "passive"))
      (node (ref "C113") (pin "2") (pinfunction "2_2") (pintype "passive"))
      (node (ref "C114") (pin "2") (pinfunction "2_2") (pintype "passive"))
      (node (ref "C115") (pin "2") (pinfunction "2_2") (pintype "passive"))
      (node (ref "C116") (pin "2") (pinfunction "2_2") (pintype "passive"))
      (node (ref "C119") (pin "2") (pinfunction "2_2") (pintype "passive"))
      (node (ref "C120") (pin "2") (pinfunction "2_2") (pintype "passive"))
      (node (ref "C121") (pin "2") (pinfunction "2_2") (pintype "passive"))
      (node (ref "C122") (pin "2") (pinfunction "2_2") (pintype "passive"))
      (node (ref "C123") (pin "2") (pinfunction "2_2") (pintype "passive"))
      (node (ref "C124") (pin "2") (pinfunction "2_2") (pintype "passive"))
      (node (ref "C125") (pin "2") (pinfunction "2_2") (pintype "passive"))
      (node (ref "C126") (pin "2") (pinfunction "2_2") (pintype "passive"))
      (node (ref "C99") (pin "2") (pinfunction "2_2") (pintype "passive"))
      (node (ref "R51") (pin "1") (pinfunction "1_1") (pintype "passive"))
      (node (ref "R64") (pin "1") (pinfunction "1_1") (pintype "passive"))
      (node (ref "R70") (pin "1") (pinfunction "1_1") (pintype "passive"))
      (node (ref "R76") (pin "1") (pinfunction "1_1") (pintype "passive"))
      (node (ref "R84") (pin "1") (pinfunction "1_1") (pintype "passive"))
      (node (ref "R85") (pin "1") (pinfunction "1_1") (pintype "passive"))
      (node (ref "R86") (pin "1") (pinfunction "1_1") (pintype "passive"))
      (node (ref "R87") (pin "1") (pinfunction "1_1") (pintype "passive"))
      (node (ref "U17") (pin "11") (pinfunction "PAD_11") (pintype "power_in"))
      (node (ref "U17") (pin "8") (pinfunction "GND_8") (pintype "power_in"))
      (node (ref "U18") (pin "11") (pinfunction "PAD_11") (pintype "power_in"))
      (node (ref "U18") (pin "8") (pinfunction "GND_8") (pintype "power_in"))
      (node (ref "U19") (pin "11") (pinfunction "PAD_11") (pintype "power_in"))
      (node (ref "U19") (pin "8") (pinfunction "GND_8") (pintype "power_in"))
      (node (ref "U20") (pin "11") (pinfunction "PAD_11") (pintype "power_in"))
      (node (ref "U20") (pin "8") (pinfunction "GND_8") (pintype "power_in"))
      (node (ref "U21") (pin "11") (pinfunction "PAD_11") (pintype "power_in"))
      (node (ref "U21") (pin "8") (pinfunction "GND_8") (pintype "power_in"))
      (node (ref "U22") (pin "11") (pinfunction "PAD_11") (pintype "power_in"))
      (node (ref "U22") (pin "8") (pinfunction "GND_8") (pintype "power_in"))
      (node (ref "U24") (pin "11") (pinfunction "PAD_11") (pintype "power_in"))
      (node (ref "U24") (pin "8") (pinfunction "GND_8") (pintype "power_in"))
      (node (ref "U25") (pin "11") (pinfunction "PAD_11") (pintype "power_in"))
      (node (ref "U25") (pin "8") (pinfunction "GND_8") (pintype "power_in"))
      (node (ref "U26") (pin "11") (pinfunction "PAD_11") (pintype "power_in"))
      (node (ref "U26") (pin "8") (pinfunction "GND_8") (pintype "power_in"))
    )
    (net (code "9") (name "Net-(U17-ILIM)") (class "Default")
      (node (ref "R55") (pin "2") (pinfunction "2_2") (pintype "passive"))
      (node (ref "U17") (pin "5") (pinfunction "ILIM_5") (pintype "output"))
    )
    (net (code "10") (name "Net-(U17-OUT)") (class "Default")
      (node (ref "C99") (pin "1") (pinfunction "1_1") (pintype "passive"))
      (node (ref "R46") (pin "1") (pinfunction "1_1") (pintype "passive"))
      (node (ref "U17") (pin "10") (pinfunction "OUT_10") (pintype "power_in"))
      (node (ref "U17") (pin "9") (pinfunction "OUTS_9") (pintype "input"))
    )
    (net (code "11") (name "Net-(U17-PG)") (class "Default")
      (node (ref "R49") (pin "1") (pinfunction "1_1") (pintype "passive"))
      (node (ref "U17") (pin "4") (pinfunction "PG_4") (pintype "output"))
    )
    (net (code "12") (name "Net-(U17-PGFB)") (class "Default")
      (node (ref "R48") (pin "1") (pinfunction "1_1") (pintype "passive"))
      (node (ref "R51") (pin "2") (pinfunction "2_2") (pintype "passive"))
      (node (ref "U17") (pin "6") (pinfunction "PGFB_6") (pintype "input"))
    )
    (net (code "13") (name "Net-(U18-ILIM)") (class "Default")
      (node (ref "R56") (pin "2") (pinfunction "2_2") (pintype "passive"))
      (node (ref "U18") (pin "5") (pinfunction "ILIM_5") (pintype "output"))
    )
    (net (code "14") (name "Net-(U18-OUT)") (class "Default")
      (node (ref "C100") (pin "1") (pinfunction "1_1") (pintype "passive"))
      (node (ref "R47") (pin "1") (pinfunction "1_1") (pintype "passive"))
      (node (ref "U18") (pin "10") (pinfunction "OUT_10") (pintype "power_in"))
      (node (ref "U18") (pin "9") (pinfunction "OUTS_9") (pintype "input"))
    )
    (net (code "15") (name "Net-(U18-PG)") (class "Default")
      (node (ref "R50") (pin "1") (pinfunction "1_1") (pintype "passive"))
      (node (ref "U18") (pin "4") (pinfunction "PG_4") (pintype "output"))
    )
    (net (code "16") (name "Net-(U19-ILIM)") (class "Default")
      (node (ref "R61") (pin "2") (pinfunction "2_2") (pintype "passive"))
      (node (ref "U19") (pin "5") (pinfunction "ILIM_5") (pintype "output"))
    )
    (net (code "17") (name "Net-(U19-OUT)") (class "Default")
      (node (ref "C104") (pin "1") (pinfunction "1_1") (pintype "passive"))
      (node (ref "R57") (pin "1") (pinfunction "1_1") (pintype "passive"))
      (node (ref "U19") (pin "10") (pinfunction "OUT_10") (pintype "power_in"))
      (node (ref "U19") (pin "9") (pinfunction "OUTS_9") (pintype "input"))
    )
    (net (code "18") (name "Net-(U19-PG)") (class "Default")
      (node (ref "R59") (pin "1") (pinfunction "1_1") (pintype "passive"))
      (node (ref "U19") (pin "4") (pinfunction "PG_4") (pintype "output"))
    )
    (net (code "19") (name "Net-(U20-ILIM)") (class "Default")
      (node (ref "R62") (pin "2") (pinfunction "2_2") (pintype "passive"))
      (node (ref "U20") (pin "5") (pinfunction "ILIM_5") (pintype "output"))
    )
    (net (code "20") (name "Net-(U20-OUT)") (class "Default")
      (node (ref "C105") (pin "1") (pinfunction "1_1") (pintype "passive"))
      (node (ref "R58") (pin "1") (pinfunction "1_1") (pintype "passive"))
      (node (ref "U20") (pin "10") (pinfunction "OUT_10") (pintype "power_in"))
      (node (ref "U20") (pin "9") (pinfunction "OUTS_9") (pintype "input"))
    )
    (net (code "21") (name "Net-(U20-PG)") (class "Default")
      (node (ref "R60") (pin "1") (pinfunction "1_1") (pintype "passive"))
      (node (ref "U20") (pin "4") (pinfunction "PG_4") (pintype "output"))
    )
    (net (code "22") (name "Net-(U21-ILIM)") (class "Default")
      (node (ref "R71") (pin "2") (pinfunction "2_2") (pintype "passive"))
      (node (ref "U21") (pin "5") (pinfunction "ILIM_5") (pintype "output"))
    )
    (net (code "23") (name "Net-(U21-OUT)") (class "Default")
      (node (ref "C112") (pin "1") (pinfunction "1_1") (pintype "passive"))
      (node (ref "R65") (pin "1") (pinfunction "1_1") (pintype "passive"))
      (node (ref "U21") (pin "10") (pinfunction "OUT_10") (pintype "power_in"))
      (node (ref "U21") (pin "9") (pinfunction "OUTS_9") (pintype "input"))
    )
    (net (code "24") (name "Net-(U21-PG)") (class "Default")
      (node (ref "R68") (pin "1") (pinfunction "1_1") (pintype "passive"))
      (node (ref "U21") (pin "4") (pinfunction "PG_4") (pintype "output"))
    )
    (net (code "25") (name "Net-(U21-PGFB)") (class "Default")
      (node (ref "R67") (pin "1") (pinfunction "1_1") (pintype "passive"))
      (node (ref "R70") (pin "2") (pinfunction "2_2") (pintype "passive"))
      (node (ref "U21") (pin "6") (pinfunction "PGFB_6") (pintype "input"))
    )
    (net (code "26") (name "Net-(U22-ILIM)") (class "Default")
      (node (ref "R72") (pin "2") (pinfunction "2_2") (pintype "passive"))
      (node (ref "U22") (pin "5") (pinfunction "ILIM_5") (pintype "output"))
    )
    (net (code "27") (name "Net-(U22-OUT)") (class "Default")
      (node (ref "C114") (pin "1") (pinfunction "1_1") (pintype "passive"))
      (node (ref "R66") (pin "1") (pinfunction "1_1") (pintype "passive"))
      (node (ref "U22") (pin "10") (pinfunction "OUT_10") (pintype "power_in"))
      (node (ref "U22") (pin "9") (pinfunction "OUTS_9") (pintype "input"))
    )
    (net (code "28") (name "Net-(U22-PG)") (class "Default")
      (node (ref "R69") (pin "1") (pinfunction "1_1") (pintype "passive"))
      (node (ref "U22") (pin "4") (pinfunction "PG_4") (pintype "output"))
    )
    (net (code "29") (name "Net-(U24-ILIM)") (class "Default")
      (node (ref "R77") (pin "2") (pinfunction "2_2") (pintype "passive"))
      (node (ref "U24") (pin "5") (pinfunction "ILIM_5") (pintype "output"))
    )
    (net (code "30") (name "Net-(U24-OUT)") (class "Default")
      (node (ref "C115") (pin "1") (pinfunction "1_1") (pintype "passive"))
      (node (ref "R73") (pin "1") (pinfunction "1_1") (pintype "passive"))
      (node (ref "U24") (pin "10") (pinfunction "OUT_10") (pintype "power_in"))
      (node (ref "U24") (pin "9") (pinfunction "OUTS_9") (pintype "input"))
    )
    (net (code "31") (name "Net-(U24-PG)") (class "Default")
      (node (ref "R75") (pin "1") (pinfunction "1_1") (pintype "passive"))
      (node (ref "U24") (pin "4") (pinfunction "PG_4") (pintype "output"))
    )
    (net (code "32") (name "Net-(U25-PG)") (class "Default")
      (node (ref "R82") (pin "1") (pinfunction "1_1") (pintype "passive"))
      (node (ref "U25") (pin "4") (pinfunction "PG_4") (pintype "output"))
    )
    (net (code "33") (name "Net-(U25-PGFB)") (class "Default")
      (node (ref "R80") (pin "1") (pinfunction "1_1") (pintype "passive"))
      (node (ref "R84") (pin "2") (pinfunction "2_2") (pintype "passive"))
      (node (ref "U25") (pin "6") (pinfunction "PGFB_6") (pintype "input"))
    )
    (net (code "34") (name "Net-(U25-SET)") (class "Default")
      (node (ref "C123") (pin "1") (pinfunction "1_1") (pintype "passive"))
      (node (ref "C124") (pin "1") (pinfunction "1_1") (pintype "passive"))
      (node (ref "R86") (pin "2") (pinfunction "2_2") (pintype "passive"))
      (node (ref "U25") (pin "7") (pinfunction "SET_7") (pintype "bidirectional"))
    )
    (net (code "35") (name "Net-(U26-PG)") (class "Default")
      (node (ref "R83") (pin "1") (pinfunction "1_1") (pintype "passive"))
      (node (ref "U26") (pin "4") (pinfunction "PG_4") (pintype "output"))
    )
    (net (code "36") (name "Net-(U26-PGFB)") (class "Default")
      (node (ref "R81") (pin "1") (pinfunction "1_1") (pintype "passive"))
      (node (ref "R85") (pin "2") (pinfunction "2_2") (pintype "passive"))
      (node (ref "U26") (pin "6") (pinfunction "PGFB_6") (pintype "input"))
    )
    (net (code "37") (name "Net-(U26-SET)") (class "Default")
      (node (ref "C125") (pin "1") (pinfunction "1_1") (pintype "passive"))
      (node (ref "C126") (pin "1") (pinfunction "1_1") (pintype "passive"))
      (node (ref "R87") (pin "2") (pinfunction "2_2") (pintype "passive"))
      (node (ref "U26") (pin "7") (pinfunction "SET_7") (pintype "bidirectional"))
    )
    (net (code "38") (name "VCC12V") (class "Default")
      (node (ref "C101") (pin "1") (pinfunction "1_1") (pintype "passive"))
      (node (ref "C102") (pin "1") (pinfunction "1_1") (pintype "passive"))
      (node (ref "C103") (pin "1") (pinfunction "1_1") (pintype "passive"))
      (node (ref "C106") (pin "1") (pinfunction "1_1") (pintype "passive"))
      (node (ref "C107") (pin "1") (pinfunction "1_1") (pintype "passive"))
      (node (ref "C110") (pin "1") (pinfunction "1_1") (pintype "passive"))
      (node (ref "C111") (pin "1") (pinfunction "1_1") (pintype "passive"))
      (node (ref "C113") (pin "1") (pinfunction "1_1") (pintype "passive"))
      (node (ref "C116") (pin "1") (pinfunction "1_1") (pintype "passive"))
      (node (ref "C119") (pin "1") (pinfunction "1_1") (pintype "passive"))
      (node (ref "C121") (pin "1") (pinfunction "1_1") (pintype "passive"))
      (node (ref "R49") (pin "2") (pinfunction "2_2") (pintype "passive"))
      (node (ref "R50") (pin "2") (pinfunction "2_2") (pintype "passive"))
      (node (ref "R59") (pin "2") (pinfunction "2_2") (pintype "passive"))
      (node (ref "R60") (pin "2") (pinfunction "2_2") (pintype "passive"))
      (node (ref "R68") (pin "2") (pinfunction "2_2") (pintype "passive"))
      (node (ref "R69") (pin "2") (pinfunction "2_2") (pintype "passive"))
      (node (ref "R75") (pin "2") (pinfunction "2_2") (pintype "passive"))
      (node (ref "R82") (pin "2") (pinfunction "2_2") (pintype "passive"))
      (node (ref "R83") (pin "2") (pinfunction "2_2") (pintype "passive"))
      (node (ref "U17") (pin "1") (pinfunction "IN_1") (pintype "power_in"))
      (node (ref "U17") (pin "2") (pinfunction "IN_2") (pintype "power_in"))
      (node (ref "U17") (pin "3") (pinfunction "EN/UV_3") (pintype "input"))
      (node (ref "U18") (pin "1") (pinfunction "IN_1") (pintype "power_in"))
      (node (ref "U18") (pin "2") (pinfunction "IN_2") (pintype "power_in"))
      (node (ref "U18") (pin "3") (pinfunction "EN/UV_3") (pintype "input"))
      (node (ref "U18") (pin "6") (pinfunction "PGFB_6") (pintype "input"))
      (node (ref "U19") (pin "1") (pinfunction "IN_1") (pintype "power_in"))
      (node (ref "U19") (pin "2") (pinfunction "IN_2") (pintype "power_in"))
      (node (ref "U19") (pin "3") (pinfunction "EN/UV_3") (pintype "input"))
      (node (ref "U19") (pin "6") (pinfunction "PGFB_6") (pintype "input"))
      (node (ref "U20") (pin "1") (pinfunction "IN_1") (pintype "power_in"))
      (node (ref "U20") (pin "2") (pinfunction "IN_2") (pintype "power_in"))
      (node (ref "U20") (pin "3") (pinfunction "EN/UV_3") (pintype "input"))
      (node (ref "U20") (pin "6") (pinfunction "PGFB_6") (pintype "input"))
      (node (ref "U21") (pin "1") (pinfunction "IN_1") (pintype "power_in"))
      (node (ref "U21") (pin "2") (pinfunction "IN_2") (pintype "power_in"))
      (node (ref "U21") (pin "3") (pinfunction "EN/UV_3") (pintype "input"))
      (node (ref "U22") (pin "1") (pinfunction "IN_1") (pintype "power_in"))
      (node (ref "U22") (pin "2") (pinfunction "IN_2") (pintype "power_in"))
      (node (ref "U22") (pin "3") (pinfunction "EN/UV_3") (pintype "input"))
      (node (ref "U22") (pin "6") (pinfunction "PGFB_6") (pintype "input"))
      (node (ref "U24") (pin "1") (pinfunction "IN_1") (pintype "power_in"))
      (node (ref "U24") (pin "2") (pinfunction "IN_2") (pintype "power_in"))
      (node (ref "U24") (pin "3") (pinfunction "EN/UV_3") (pintype "input"))
      (node (ref "U24") (pin "6") (pinfunction "PGFB_6") (pintype "input"))
      (node (ref "U25") (pin "1") (pinfunction "IN_1") (pintype "power_in"))
      (node (ref "U25") (pin "2") (pinfunction "IN_2") (pintype "power_in"))
      (node (ref "U25") (pin "3") (pinfunction "EN/UV_3") (pintype "input"))
      (node (ref "U26") (pin "1") (pinfunction "IN_1") (pintype "power_in"))
      (node (ref "U26") (pin "2") (pinfunction "IN_2") (pintype "power_in"))
      (node (ref "U26") (pin "3") (pinfunction "EN/UV_3") (pintype "input"))
    )
    (net (code "39") (name "VCO_VCC") (class "Default")
      (node (ref "C120") (pin "1") (pinfunction "1_1") (pintype "passive"))
      (node (ref "R80") (pin "2") (pinfunction "2_2") (pintype "passive"))
      (node (ref "U25") (pin "10") (pinfunction "OUT_10") (pintype "power_in"))
      (node (ref "U25") (pin "9") (pinfunction "OUTS_9") (pintype "input"))
    )
    (net (code "40") (name "unconnected-(R44-Pad1)") (class "Default")
      (node (ref "R44") (pin "1") (pinfunction "1_1") (pintype "passive"))
    )
    (net (code "41") (name "unconnected-(R44-Pad2)") (class "Default")
      (node (ref "R44") (pin "2") (pinfunction "2_2") (pintype "passive"))
    )
    (net (code "42") (name "unconnected-(R45-Pad1)") (class "Default")
      (node (ref "R45") (pin "1") (pinfunction "1_1") (pintype "passive"))
    )
    (net (code "43") (name "unconnected-(R45-Pad2)") (class "Default")
      (node (ref "R45") (pin "2") (pinfunction "2_2") (pintype "passive"))
    )
    (net (code "44") (name "unconnected-(U25-ILIM-Pad5)") (class "Default")
      (node (ref "U25") (pin "5") (pinfunction "ILIM_5") (pintype "output"))
    )
    (net (code "45") (name "unconnected-(U26-ILIM-Pad5)") (class "Default")
      (node (ref "U26") (pin "5") (pinfunction "ILIM_5") (pintype "output"))
    )
  )
)
